# Main.net
KiCad netlist of a schematic drawn in Altium Designer
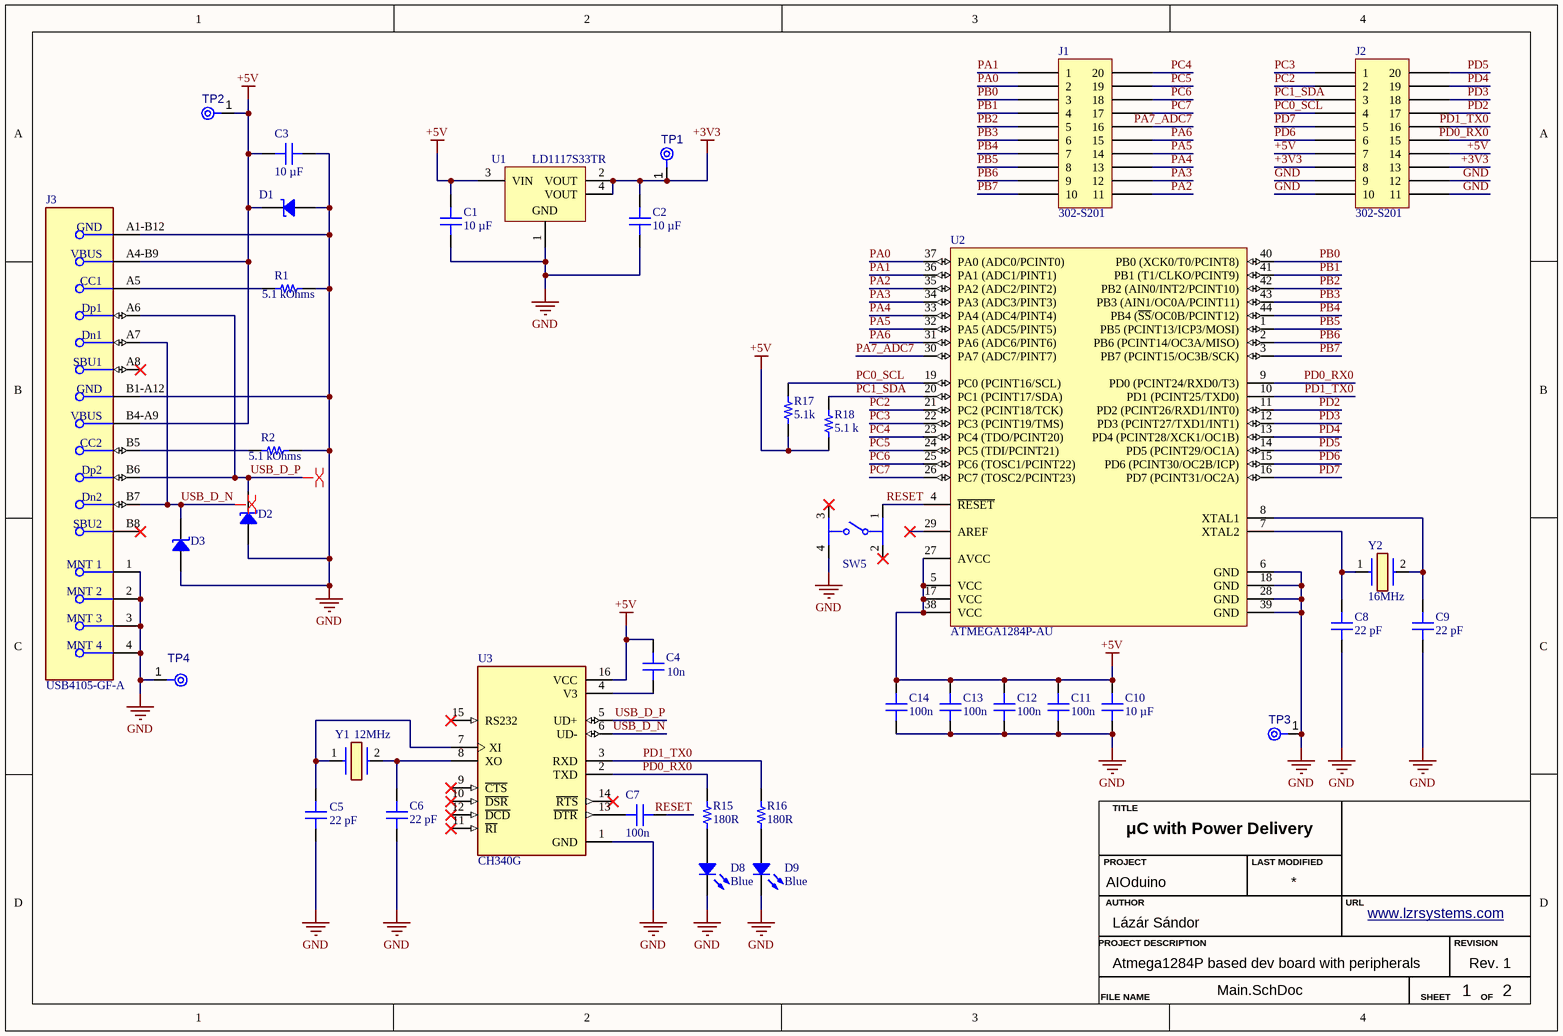
[diagram p0: Main.SchDoc]

(export (version "E")
  (design (tool "Eeschema 10.0.6"))
  (components
    (comp (ref "C1")
      (value "10 µF")
      (footprint "CAP 1206_3216 - 0.8MM")
      (description "CAP CER 10UF 35V X5R 1206")
      (fields
        (field (name "PART NUMBER") "GRT31CR6YA106KE01K")
        (field (name "CAPACITANCE") "10 µF")
        (field (name "MANUFACTURER") "Murata Electronics")
      )
      (libsource (lib "Celestial Altium Library - altium_library") (part "Capacitor"))
    )
    (comp (ref "C2")
      (value "10 µF")
      (footprint "CAP 1206_3216 - 0.8MM")
      (description "CAP CER 10UF 35V X5R 1206")
      (fields
        (field (name "PART NUMBER") "GRT31CR6YA106KE01K")
        (field (name "CAPACITANCE") "10 µF")
        (field (name "MANUFACTURER") "Murata Electronics")
      )
      (libsource (lib "Celestial Altium Library - altium_library") (part "Capacitor"))
    )
    (comp (ref "C3")
      (value "10 µF")
      (footprint "CAP 1206_3216 - 0.8MM")
      (description "CAP CER 10UF 35V X5R 1206")
      (fields
        (field (name "PART NUMBER") "GRT31CR6YA106KE01K")
        (field (name "CAPACITANCE") "10 µF")
        (field (name "MANUFACTURER") "Murata Electronics")
      )
      (libsource (lib "Celestial Altium Library - altium_library") (part "Capacitor"))
    )
    (comp (ref "C4")
      (value "10000 pF")
      (footprint "CAP 0805_2012")
      (description "CAP CER 0805 10NF 100V X7R")
      (fields
        (field (name "PART NUMBER") "C0805X103K1RAC3316")
        (field (name "CAPACITANCE") "10n")
        (field (name "MANUFACTURER") "KEMET")
      )
      (libsource (lib "Celestial Altium Library - altium_library") (part "Capacitor"))
    )
    (comp (ref "C5")
      (value "22 pF")
      (footprint "CAP 0805_2012")
      (description "CAP CER 22PF 50V C0G/NP0 0805")
      (fields
        (field (name "PART NUMBER") "C0805C220J5GACAUTO")
        (field (name "CAPACITANCE") "22 pF")
        (field (name "MANUFACTURER") "KEMET")
      )
      (libsource (lib "Celestial Altium Library - altium_library") (part "Capacitor"))
    )
    (comp (ref "C6")
      (value "22 pF")
      (footprint "CAP 0805_2012")
      (description "CAP CER 22PF 50V C0G/NP0 0805")
      (fields
        (field (name "PART NUMBER") "C0805C220J5GACAUTO")
        (field (name "CAPACITANCE") "22 pF")
        (field (name "MANUFACTURER") "KEMET")
      )
      (libsource (lib "Celestial Altium Library - altium_library") (part "Capacitor"))
    )
    (comp (ref "C7")
      (value "0.1 µF")
      (footprint "CAP 0805_2012")
      (description "CAP CER 0.1UF 50V X7R 0805")
      (fields
        (field (name "PART NUMBER") "CC0805MRX7R9BB104")
        (field (name "CAPACITANCE") "100n")
        (field (name "MANUFACTURER") "Yageo")
      )
      (libsource (lib "Celestial Altium Library - altium_library") (part "Capacitor"))
    )
    (comp (ref "C8")
      (value "22 pF")
      (footprint "CAP 0805_2012")
      (description "CAP CER 22PF 50V C0G/NP0 0805")
      (fields
        (field (name "PART NUMBER") "C0805C220J5GACAUTO")
        (field (name "CAPACITANCE") "22 pF")
        (field (name "MANUFACTURER") "KEMET")
      )
      (libsource (lib "Celestial Altium Library - altium_library") (part "Capacitor"))
    )
    (comp (ref "C9")
      (value "22 pF")
      (footprint "CAP 0805_2012")
      (description "CAP CER 22PF 50V C0G/NP0 0805")
      (fields
        (field (name "PART NUMBER") "C0805C220J5GACAUTO")
        (field (name "CAPACITANCE") "22 pF")
        (field (name "MANUFACTURER") "KEMET")
      )
      (libsource (lib "Celestial Altium Library - altium_library") (part "Capacitor"))
    )
    (comp (ref "C10")
      (value "10 µF")
      (footprint "CAP 1206_3216 - 0.8MM")
      (description "CAP CER 10UF 35V X5R 1206")
      (fields
        (field (name "PART NUMBER") "GRT31CR6YA106KE01K")
        (field (name "CAPACITANCE") "10 µF")
        (field (name "MANUFACTURER") "Murata Electronics")
      )
      (libsource (lib "Celestial Altium Library - altium_library") (part "Capacitor"))
    )
    (comp (ref "C11")
      (value "0.1 µF")
      (footprint "CAP 0805_2012")
      (description "CAP CER 0.1UF 50V X7R 0805")
      (fields
        (field (name "PART NUMBER") "CC0805MRX7R9BB104")
        (field (name "CAPACITANCE") "100n")
        (field (name "MANUFACTURER") "Yageo")
      )
      (libsource (lib "Celestial Altium Library - altium_library") (part "Capacitor"))
    )
    (comp (ref "C12")
      (value "0.1 µF")
      (footprint "CAP 0805_2012")
      (description "CAP CER 0.1UF 50V X7R 0805")
      (fields
        (field (name "PART NUMBER") "CC0805MRX7R9BB104")
        (field (name "CAPACITANCE") "100n")
        (field (name "MANUFACTURER") "Yageo")
      )
      (libsource (lib "Celestial Altium Library - altium_library") (part "Capacitor"))
    )
    (comp (ref "C13")
      (value "0.1 µF")
      (footprint "CAP 0805_2012")
      (description "CAP CER 0.1UF 50V X7R 0805")
      (fields
        (field (name "PART NUMBER") "CC0805MRX7R9BB104")
        (field (name "CAPACITANCE") "100n")
        (field (name "MANUFACTURER") "Yageo")
      )
      (libsource (lib "Celestial Altium Library - altium_library") (part "Capacitor"))
    )
    (comp (ref "C14")
      (value "0.1 µF")
      (footprint "CAP 0805_2012")
      (description "CAP CER 0.1UF 50V X7R 0805")
      (fields
        (field (name "PART NUMBER") "CC0805MRX7R9BB104")
        (field (name "CAPACITANCE") "100n")
        (field (name "MANUFACTURER") "Yageo")
      )
      (libsource (lib "Celestial Altium Library - altium_library") (part "Capacitor"))
    )
    (comp (ref "D1")
      (value "PESD5V0S1UB,115")
      (footprint "SOD523F")
      (description "TVS DIODE 5VWM 20VC SOD523")
      (fields (field (name "MANUFACTURER") "Nexperia USA Inc."))
      (libsource (lib "Celestial Altium Library - altium_library") (part "DIODE TVS UNI"))
    )
    (comp (ref "D2")
      (value "PESD5V0S1UB,115")
      (footprint "SOD523F")
      (description "TVS DIODE 5VWM 20VC SOD523")
      (fields (field (name "MANUFACTURER") "Nexperia USA Inc."))
      (libsource (lib "Celestial Altium Library - altium_library") (part "DIODE TVS UNI"))
    )
    (comp (ref "D3")
      (value "PESD5V0S1UB,115")
      (footprint "SOD523F")
      (description "TVS DIODE 5VWM 20VC SOD523")
      (fields (field (name "MANUFACTURER") "Nexperia USA Inc."))
      (libsource (lib "Celestial Altium Library - altium_library") (part "DIODE TVS UNI"))
    )
    (comp (ref "D8")
      (value "Blue")
      (footprint "LED 1206_3216 BLUE")
      (description "LED BLUE CLEAR 1206 SMD")
      (fields
        (field (name "PART NUMBER") "SML-LX1206USBC-TR")
        (field (name "MANUFACTURER") "Lumex Opto/Components Inc.")
      )
      (libsource (lib "Celestial Altium Library - altium_library") (part "LED"))
    )
    (comp (ref "D9")
      (value "Blue")
      (footprint "LED 1206_3216 BLUE")
      (description "LED BLUE CLEAR 1206 SMD")
      (fields
        (field (name "PART NUMBER") "SML-LX1206USBC-TR")
        (field (name "MANUFACTURER") "Lumex Opto/Components Inc.")
      )
      (libsource (lib "Celestial Altium Library - altium_library") (part "LED"))
    )
    (comp (ref "J1")
      (value "302-S201")
      (footprint "OST 302-S201")
      (description "CONN HEADER VERT 20POS 2.54MM")
      (fields (field (name "MANUFACTURER") "On Shore Technology Inc."))
      (libsource (lib "Celestial Altium Library - altium_library") (part "20 Pin Dual Row"))
    )
    (comp (ref "J2")
      (value "302-S201")
      (footprint "OST 302-S201")
      (description "CONN HEADER VERT 20POS 2.54MM")
      (fields (field (name "MANUFACTURER") "On Shore Technology Inc."))
      (libsource (lib "Celestial Altium Library - altium_library") (part "20 Pin Dual Row"))
    )
    (comp (ref "J3")
      (value "USB4105-GF-A")
      (footprint "FP-USB4105-GF-A-MFG")
      (description "Conn USB 2.0 Type C RCP 24 POS 0.3mm/0.5mm Solder RA SMD 24 Terminal 1 Port T/R")
      (libsource (lib "Sandor Lazar") (part "e7c17a616881a82b79941196b4bec10"))
    )
    (comp (ref "R1")
      (value "5.1 kOhms")
      (footprint "RES 0805_2012")
      (description "RES 5.1K OHM 1% 1/8W 0805")
      (fields
        (field (name "PART NUMBER") "RMCF0805FT5K10")
        (field (name "MANUFACTURER") "Stackpole Electronics Inc")
      )
      (libsource (lib "Celestial Altium Library - altium_library") (part "Resistor"))
    )
    (comp (ref "R2")
      (value "5.1 kOhms")
      (footprint "RES 0805_2012")
      (description "RES 5.1K OHM 1% 1/8W 0805")
      (fields
        (field (name "PART NUMBER") "RMCF0805FT5K10")
        (field (name "MANUFACTURER") "Stackpole Electronics Inc")
      )
      (libsource (lib "Celestial Altium Library - altium_library") (part "Resistor"))
    )
    (comp (ref "R15")
      (value "180R")
      (footprint "RES 0805_2012")
      (description "RES SMD 180 OHM 1% 1/2W 0805")
      (fields (field (name "PART NUMBER") "CRCW0805180RFKEAHP") (field (name "MANUFACTURER") "Vishay Dale"))
      (libsource (lib "Celestial Altium Library - altium_library") (part "Resistor"))
    )
    (comp (ref "R16")
      (value "180R")
      (footprint "RES 0805_2012")
      (description "RES SMD 180 OHM 1% 1/2W 0805")
      (fields (field (name "PART NUMBER") "CRCW0805180RFKEAHP") (field (name "MANUFACTURER") "Vishay Dale"))
      (libsource (lib "Celestial Altium Library - altium_library") (part "Resistor"))
    )
    (comp (ref "R17")
      (value "5.1k")
      (footprint "RES 0805_2012")
      (description "RES 5.1K OHM 1% 1/8W 0805")
      (fields
        (field (name "PART NUMBER") "RMCF0805FT5K10")
        (field (name "MANUFACTURER") "Stackpole Electronics Inc")
      )
      (libsource (lib "Celestial Altium Library - altium_library") (part "Resistor"))
    )
    (comp (ref "R18")
      (value "5.1 k")
      (footprint "RES 0805_2012")
      (description "RES 5.1K OHM 1% 1/8W 0805")
      (fields
        (field (name "PART NUMBER") "RMCF0805FT5K10")
        (field (name "MANUFACTURER") "Stackpole Electronics Inc")
      )
      (libsource (lib "Celestial Altium Library - altium_library") (part "Resistor"))
    )
    (comp (ref "SW5")
      (value "PTS526SK15SMTR2LFS")
      (footprint "FP-PTS526SK15SMTR2LFS-MFG")
      (description "Switch Tactile N.O. SPST Round Button Gull Wing 0.05A 12VDC 200000Cycles 2.45N SMD T/R")
      (libsource (lib "Sandor Lazar") (part "b8895f3f4cefb76e1819d2863dba89b"))
    )
    (comp (ref "TP1")
      (value "TPAD6R")
      (footprint "TP06R")
      (description "0.6mm round")
      (libsource (lib "Sandor Lazar") (part "CMP-001-0001-4"))
    )
    (comp (ref "TP2")
      (value "TPAD6R")
      (footprint "TP06R")
      (description "0.6mm round")
      (libsource (lib "Sandor Lazar") (part "CMP-001-0001-4"))
    )
    (comp (ref "TP3")
      (value "TPAD6R")
      (footprint "TP06R")
      (description "0.6mm round")
      (libsource (lib "Sandor Lazar") (part "CMP-001-0001-4"))
    )
    (comp (ref "TP4")
      (value "TPAD6R")
      (footprint "TP06R")
      (description "0.6mm round")
      (libsource (lib "Sandor Lazar") (part "CMP-001-0001-4"))
    )
    (comp (ref "U1")
      (value "LD1117S33TR")
      (footprint "STM-SOT-223_M")
      (fields (field (name "POWER") "12W") (field (name "MANUFACTURER") "STMicroelectronics"))
      (libsource (lib "Sandor Lazar") (part "STM-LD1117-SOT223-4"))
    )
    (comp (ref "U2")
      (value "ATMEGA1284P-AU")
      (footprint "ATML-44A_M")
      (fields (field (name "MANUFACTURER") "Atmel"))
      (libsource (lib "Sandor Lazar") (part "ATML-ATMEGA1284P-AU-TQFP-44"))
    )
    (comp (ref "U3")
      (value "CH340G")
      (footprint "SOIC127P600X180-16N")
      (description "USB Interface Integrated Circuit")
      (fields (field (name "MF") "WCH") (field (name "MP") "Ch340G"))
      (libsource (lib "Sandor Lazar") (part "CH340G"))
    )
    (comp (ref "Y1")
      (value "12MHz")
      (footprint "SamacSys:ECS160184XCKM")
      (description "Crystal or Oscillator")
      (fields
        (field (name "MANUFACTURER_PART_NUMBER") "ECS-160-18-4X-CKM")
        (field (name "MOUSER PART NUMBER") "520-ECS160-18-4X-CKM")
      )
      (libsource (lib "*") (part "ECS-160-18-4X-CKM"))
    )
    (comp (ref "Y2")
      (value "16MHz")
      (footprint "SamacSys:ECS160184XCKM")
      (description "Crystal or Oscillator")
      (fields
        (field (name "MANUFACTURER_PART_NUMBER") "ECS-160-18-4X-CKM")
        (field (name "MOUSER PART NUMBER") "520-ECS160-18-4X-CKM")
      )
      (libsource (lib "*") (part "ECS-160-18-4X-CKM"))
    )
  )
  (nets
    (net (code "1") (name "+3V3") (class "Default")
      (node (ref "C2") (pin "2") (pinfunction "2_2") (pintype "passive"))
      (node (ref "J2") (pin "13") (pinfunction "13_13") (pintype "passive"))
      (node (ref "J2") (pin "8") (pinfunction "8_8") (pintype "passive"))
      (node (ref "TP1") (pin "1") (pinfunction "TP_1") (pintype "passive"))
      (node (ref "U1") (pin "2") (pinfunction "VOUT_2") (pintype "power_in"))
      (node (ref "U1") (pin "4") (pinfunction "VOUT_4") (pintype "power_in"))
    )
    (net (code "2") (name "+5V") (class "Default")
      (node (ref "C1") (pin "2") (pinfunction "2_2") (pintype "passive"))
      (node (ref "C10") (pin "2") (pinfunction "2_2") (pintype "passive"))
      (node (ref "C11") (pin "2") (pinfunction "2_2") (pintype "passive"))
      (node (ref "C12") (pin "2") (pinfunction "2_2") (pintype "passive"))
      (node (ref "C13") (pin "1") (pinfunction "1_1") (pintype "passive"))
      (node (ref "C14") (pin "2") (pinfunction "2_2") (pintype "passive"))
      (node (ref "C3") (pin "1") (pinfunction "1_1") (pintype "passive"))
      (node (ref "C4") (pin "2") (pinfunction "2_2") (pintype "passive"))
      (node (ref "D1") (pin "2") (pinfunction "2_2") (pintype "passive"))
      (node (ref "J2") (pin "14") (pinfunction "14_14") (pintype "passive"))
      (node (ref "J2") (pin "7") (pinfunction "7_7") (pintype "passive"))
      (node (ref "J3") (pin "A4-B9") (pinfunction "VBUS_A4-B9") (pintype "passive"))
      (node (ref "J3") (pin "B4-A9") (pinfunction "VBUS_B4-A9") (pintype "passive"))
      (node (ref "R17") (pin "1") (pinfunction "1_1") (pintype "passive"))
      (node (ref "R18") (pin "1") (pinfunction "1_1") (pintype "passive"))
      (node (ref "TP2") (pin "1") (pinfunction "TP_1") (pintype "passive"))
      (node (ref "U1") (pin "3") (pinfunction "VIN_3") (pintype "power_in"))
      (node (ref "U2") (pin "17") (pinfunction "VCC_17") (pintype "power_in"))
      (node (ref "U2") (pin "27") (pinfunction "AVCC_27") (pintype "power_in"))
      (node (ref "U2") (pin "38") (pinfunction "VCC_38") (pintype "power_in"))
      (node (ref "U2") (pin "5") (pinfunction "VCC_5") (pintype "power_in"))
      (node (ref "U3") (pin "16") (pinfunction "VCC_16") (pintype "power_in"))
    )
    (net (code "3") (name "/PA0") (class "Default")
      (node (ref "J1") (pin "2") (pinfunction "2_2") (pintype "passive"))
      (node (ref "U2") (pin "37") (pinfunction "PA0_(ADC0/PCINT0)_37") (pintype "bidirectional"))
    )
    (net (code "4") (name "/PA1") (class "Default")
      (node (ref "J1") (pin "1") (pinfunction "1_1") (pintype "passive"))
      (node (ref "U2") (pin "36") (pinfunction "PA1_(ADC1/PINT1)_36") (pintype "bidirectional"))
    )
    (net (code "5") (name "/PA2") (class "Default")
      (node (ref "J1") (pin "11") (pinfunction "11_11") (pintype "passive"))
      (node (ref "U2") (pin "35") (pinfunction "PA2_(ADC2/PINT2)_35") (pintype "bidirectional"))
    )
    (net (code "6") (name "/PA3") (class "Default")
      (node (ref "J1") (pin "12") (pinfunction "12_12") (pintype "passive"))
      (node (ref "U2") (pin "34") (pinfunction "PA3_(ADC3/PINT3)_34") (pintype "bidirectional"))
    )
    (net (code "7") (name "/PA4") (class "Default")
      (node (ref "J1") (pin "13") (pinfunction "13_13") (pintype "passive"))
      (node (ref "U2") (pin "33") (pinfunction "PA4_(ADC4/PINT4)_33") (pintype "bidirectional"))
    )
    (net (code "8") (name "/PA5") (class "Default")
      (node (ref "J1") (pin "14") (pinfunction "14_14") (pintype "passive"))
      (node (ref "U2") (pin "32") (pinfunction "PA5_(ADC5/PINT5)_32") (pintype "bidirectional"))
    )
    (net (code "9") (name "/PA6") (class "Default")
      (node (ref "J1") (pin "15") (pinfunction "15_15") (pintype "passive"))
      (node (ref "U2") (pin "31") (pinfunction "PA6_(ADC6/PINT6)_31") (pintype "bidirectional"))
    )
    (net (code "10") (name "/PA7_ADC7") (class "Default")
      (node (ref "J1") (pin "16") (pinfunction "16_16") (pintype "passive"))
      (node (ref "U2") (pin "30") (pinfunction "PA7_(ADC7/PINT7)_30") (pintype "bidirectional"))
    )
    (net (code "11") (name "/PB0") (class "Default")
      (node (ref "J1") (pin "3") (pinfunction "3_3") (pintype "passive"))
      (node (ref "U2") (pin "40") (pinfunction "PB0_(XCK0/T0/PCINT8)_40") (pintype "bidirectional"))
    )
    (net (code "12") (name "/PB1") (class "Default")
      (node (ref "J1") (pin "4") (pinfunction "4_4") (pintype "passive"))
      (node (ref "U2") (pin "41") (pinfunction "PB1_(T1/CLKO/PCINT9)_41") (pintype "bidirectional"))
    )
    (net (code "13") (name "/PB2") (class "Default")
      (node (ref "J1") (pin "5") (pinfunction "5_5") (pintype "passive"))
      (node (ref "U2") (pin "42") (pinfunction "PB2_(AIN0/INT2/PCINT10)_42") (pintype "bidirectional"))
    )
    (net (code "14") (name "/PB3") (class "Default")
      (node (ref "J1") (pin "6") (pinfunction "6_6") (pintype "passive"))
      (node (ref "U2") (pin "43") (pinfunction "PB3_(AIN1/OC0A/PCINT11)_43") (pintype "bidirectional"))
    )
    (net (code "15") (name "/PB4") (class "Default")
      (node (ref "J1") (pin "7") (pinfunction "7_7") (pintype "passive"))
      (node (ref "U2") (pin "44") (pinfunction "PB4_(~{SS}/OC0B/PCINT12)_44") (pintype "bidirectional"))
    )
    (net (code "16") (name "/PB5") (class "Default")
      (node (ref "J1") (pin "8") (pinfunction "8_8") (pintype "passive"))
      (node (ref "U2") (pin "1") (pinfunction "PB5_(PCINT13/ICP3/MOSI)_1") (pintype "bidirectional"))
    )
    (net (code "17") (name "/PB6") (class "Default")
      (node (ref "J1") (pin "9") (pinfunction "9_9") (pintype "passive"))
      (node (ref "U2") (pin "2") (pinfunction "PB6_(PCINT14/OC3A/MISO)_2") (pintype "bidirectional"))
    )
    (net (code "18") (name "/PB7") (class "Default")
      (node (ref "J1") (pin "10") (pinfunction "10_10") (pintype "passive"))
      (node (ref "U2") (pin "3") (pinfunction "PB7_(PCINT15/OC3B/SCK)_3") (pintype "bidirectional"))
    )
    (net (code "19") (name "/PC0_SCL") (class "Default")
      (node (ref "J2") (pin "4") (pinfunction "4_4") (pintype "passive"))
      (node (ref "R17") (pin "2") (pinfunction "2_2") (pintype "passive"))
      (node (ref "U2") (pin "19") (pinfunction "PC0_(PCINT16/SCL)_19") (pintype "bidirectional"))
    )
    (net (code "20") (name "/PC1_SDA") (class "Default")
      (node (ref "J2") (pin "3") (pinfunction "3_3") (pintype "passive"))
      (node (ref "R18") (pin "2") (pinfunction "2_2") (pintype "passive"))
      (node (ref "U2") (pin "20") (pinfunction "PC1_(PCINT17/SDA)_20") (pintype "bidirectional"))
    )
    (net (code "21") (name "/PC2") (class "Default")
      (node (ref "J2") (pin "2") (pinfunction "2_2") (pintype "passive"))
      (node (ref "U2") (pin "21") (pinfunction "PC2_(PCINT18/TCK)_21") (pintype "bidirectional"))
    )
    (net (code "22") (name "/PC3") (class "Default")
      (node (ref "J2") (pin "1") (pinfunction "1_1") (pintype "passive"))
      (node (ref "U2") (pin "22") (pinfunction "PC3_(PCINT19/TMS)_22") (pintype "bidirectional"))
    )
    (net (code "23") (name "/PC4") (class "Default")
      (node (ref "J1") (pin "20") (pinfunction "20_20") (pintype "passive"))
      (node (ref "U2") (pin "23") (pinfunction "PC4_(TDO/PCINT20)_23") (pintype "bidirectional"))
    )
    (net (code "24") (name "/PC5") (class "Default")
      (node (ref "J1") (pin "19") (pinfunction "19_19") (pintype "passive"))
      (node (ref "U2") (pin "24") (pinfunction "PC5_(TDI/PCINT21)_24") (pintype "bidirectional"))
    )
    (net (code "25") (name "/PC6") (class "Default")
      (node (ref "J1") (pin "18") (pinfunction "18_18") (pintype "passive"))
      (node (ref "U2") (pin "25") (pinfunction "PC6_(TOSC1/PCINT22)_25") (pintype "bidirectional"))
    )
    (net (code "26") (name "/PC7") (class "Default")
      (node (ref "J1") (pin "17") (pinfunction "17_17") (pintype "passive"))
      (node (ref "U2") (pin "26") (pinfunction "PC7_(TOSC2/PCINT23)_26") (pintype "bidirectional"))
    )
    (net (code "27") (name "/PD0_RX0") (class "Default")
      (node (ref "J2") (pin "15") (pinfunction "15_15") (pintype "passive"))
      (node (ref "R15") (pin "2") (pinfunction "2_2") (pintype "passive"))
      (node (ref "U2") (pin "9") (pinfunction "PD0_(PCINT24/RXD0/T3)_9") (pintype "passive"))
      (node (ref "U3") (pin "2") (pinfunction "TXD_2") (pintype "passive"))
    )
    (net (code "28") (name "/PD1_TX0") (class "Default")
      (node (ref "J2") (pin "16") (pinfunction "16_16") (pintype "passive"))
      (node (ref "R16") (pin "2") (pinfunction "2_2") (pintype "passive"))
      (node (ref "U2") (pin "10") (pinfunction "PD1_(PCINT25/TXD0)_10") (pintype "passive"))
      (node (ref "U3") (pin "3") (pinfunction "RXD_3") (pintype "passive"))
    )
    (net (code "29") (name "/PD2") (class "Default")
      (node (ref "J2") (pin "17") (pinfunction "17_17") (pintype "passive"))
      (node (ref "U2") (pin "11") (pinfunction "PD2_(PCINT26/RXD1/INT0)_11") (pintype "bidirectional"))
    )
    (net (code "30") (name "/PD3") (class "Default")
      (node (ref "J2") (pin "18") (pinfunction "18_18") (pintype "passive"))
      (node (ref "U2") (pin "12") (pinfunction "PD3_(PCINT27/TXD1/INT1)_12") (pintype "bidirectional"))
    )
    (net (code "31") (name "/PD4") (class "Default")
      (node (ref "J2") (pin "19") (pinfunction "19_19") (pintype "passive"))
      (node (ref "U2") (pin "13") (pinfunction "PD4_(PCINT28/XCK1/OC1B)_13") (pintype "bidirectional"))
    )
    (net (code "32") (name "/PD5") (class "Default")
      (node (ref "J2") (pin "20") (pinfunction "20_20") (pintype "passive"))
      (node (ref "U2") (pin "14") (pinfunction "PD5_(PCINT29/OC1A)_14") (pintype "bidirectional"))
    )
    (net (code "33") (name "/PD6") (class "Default")
      (node (ref "J2") (pin "6") (pinfunction "6_6") (pintype "passive"))
      (node (ref "U2") (pin "15") (pinfunction "PD6_(PCINT30/OC2B/ICP)_15") (pintype "bidirectional"))
    )
    (net (code "34") (name "/PD7") (class "Default")
      (node (ref "J2") (pin "5") (pinfunction "5_5") (pintype "passive"))
      (node (ref "U2") (pin "16") (pinfunction "PD7_(PCINT31/OC2A)_16") (pintype "bidirectional"))
    )
    (net (code "35") (name "/RESET") (class "Default")
      (node (ref "C7") (pin "2") (pinfunction "2_2") (pintype "passive"))
      (node (ref "SW5") (pin "1") (pinfunction "1_1") (pintype "passive"))
      (node (ref "U2") (pin "4") (pinfunction "~{RESET}_4") (pintype "passive"))
    )
    (net (code "36") (name "/USB_D_N") (class "Default")
      (node (ref "D3") (pin "2") (pinfunction "2_2") (pintype "passive"))
      (node (ref "J3") (pin "A7") (pinfunction "Dn1_A7") (pintype "bidirectional"))
      (node (ref "J3") (pin "B7") (pinfunction "Dn2_B7") (pintype "bidirectional"))
      (node (ref "U3") (pin "6") (pinfunction "UD-_6") (pintype "bidirectional"))
    )
    (net (code "37") (name "/USB_D_P") (class "Default")
      (node (ref "D2") (pin "2") (pinfunction "2_2") (pintype "passive"))
      (node (ref "J3") (pin "A6") (pinfunction "Dp1_A6") (pintype "bidirectional"))
      (node (ref "J3") (pin "B6") (pinfunction "Dp2_B6") (pintype "bidirectional"))
      (node (ref "U3") (pin "5") (pinfunction "UD+_5") (pintype "bidirectional"))
    )
    (net (code "38") (name "GND") (class "Default")
      (node (ref "C1") (pin "1") (pinfunction "1_1") (pintype "passive"))
      (node (ref "C10") (pin "1") (pinfunction "1_1") (pintype "passive"))
      (node (ref "C11") (pin "1") (pinfunction "1_1") (pintype "passive"))
      (node (ref "C12") (pin "1") (pinfunction "1_1") (pintype "passive"))
      (node (ref "C13") (pin "2") (pinfunction "2_2") (pintype "passive"))
      (node (ref "C14") (pin "1") (pinfunction "1_1") (pintype "passive"))
      (node (ref "C2") (pin "1") (pinfunction "1_1") (pintype "passive"))
      (node (ref "C3") (pin "2") (pinfunction "2_2") (pintype "passive"))
      (node (ref "C5") (pin "1") (pinfunction "1_1") (pintype "passive"))
      (node (ref "C6") (pin "1") (pinfunction "1_1") (pintype "passive"))
      (node (ref "C8") (pin "1") (pinfunction "1_1") (pintype "passive"))
      (node (ref "C9") (pin "1") (pinfunction "1_1") (pintype "passive"))
      (node (ref "D1") (pin "1") (pinfunction "1_1") (pintype "passive"))
      (node (ref "D2") (pin "1") (pinfunction "1_1") (pintype "passive"))
      (node (ref "D3") (pin "1") (pinfunction "1_1") (pintype "passive"))
      (node (ref "D8") (pin "2") (pinfunction "2_2") (pintype "passive"))
      (node (ref "D9") (pin "2") (pinfunction "2_2") (pintype "passive"))
      (node (ref "J2") (pin "10") (pinfunction "10_10") (pintype "passive"))
      (node (ref "J2") (pin "11") (pinfunction "11_11") (pintype "passive"))
      (node (ref "J2") (pin "12") (pinfunction "12_12") (pintype "passive"))
      (node (ref "J2") (pin "9") (pinfunction "9_9") (pintype "passive"))
      (node (ref "J3") (pin "1") (pinfunction "MNT_1_1") (pintype "passive"))
      (node (ref "J3") (pin "2") (pinfunction "MNT_2_2") (pintype "passive"))
      (node (ref "J3") (pin "3") (pinfunction "MNT_3_3") (pintype "passive"))
      (node (ref "J3") (pin "4") (pinfunction "MNT_4_4") (pintype "passive"))
      (node (ref "J3") (pin "A1-B12") (pinfunction "GND_A1-B12") (pintype "passive"))
      (node (ref "J3") (pin "B1-A12") (pinfunction "GND_B1-A12") (pintype "passive"))
      (node (ref "R1") (pin "2") (pinfunction "2_2") (pintype "passive"))
      (node (ref "R2") (pin "2") (pinfunction "2_2") (pintype "passive"))
      (node (ref "SW5") (pin "4") (pinfunction "4_4") (pintype "passive"))
      (node (ref "TP3") (pin "1") (pinfunction "TP_1") (pintype "passive"))
      (node (ref "TP4") (pin "1") (pinfunction "TP_1") (pintype "passive"))
      (node (ref "U1") (pin "1") (pinfunction "GND_1") (pintype "power_in"))
      (node (ref "U2") (pin "18") (pinfunction "GND_18") (pintype "passive"))
      (node (ref "U2") (pin "28") (pinfunction "GND_28") (pintype "passive"))
      (node (ref "U2") (pin "39") (pinfunction "GND_39") (pintype "passive"))
      (node (ref "U2") (pin "6") (pinfunction "GND_6") (pintype "passive"))
      (node (ref "U3") (pin "1") (pinfunction "GND_1") (pintype "power_in"))
    )
    (net (code "39") (name "Net-(D8-Pad1)") (class "Default")
      (node (ref "D8") (pin "1") (pinfunction "1_1") (pintype "passive"))
      (node (ref "R15") (pin "1") (pinfunction "1_1") (pintype "passive"))
    )
    (net (code "40") (name "Net-(D9-Pad1)") (class "Default")
      (node (ref "D9") (pin "1") (pinfunction "1_1") (pintype "passive"))
      (node (ref "R16") (pin "1") (pinfunction "1_1") (pintype "passive"))
    )
    (net (code "41") (name "Net-(J3-CC1)") (class "Default")
      (node (ref "J3") (pin "A5") (pinfunction "CC1_A5") (pintype "passive"))
      (node (ref "R1") (pin "1") (pinfunction "1_1") (pintype "passive"))
    )
    (net (code "42") (name "Net-(J3-CC2)") (class "Default")
      (node (ref "J3") (pin "B5") (pinfunction "CC2_B5") (pintype "bidirectional"))
      (node (ref "R2") (pin "1") (pinfunction "1_1") (pintype "passive"))
    )
    (net (code "43") (name "Net-(U2-XTAL1)") (class "Default")
      (node (ref "C9") (pin "2") (pinfunction "2_2") (pintype "passive"))
      (node (ref "U2") (pin "8") (pinfunction "XTAL1_8") (pintype "passive"))
      (node (ref "Y2") (pin "2") (pinfunction "CRYSTAL_2_2") (pintype "passive"))
    )
    (net (code "44") (name "Net-(U2-XTAL2)") (class "Default")
      (node (ref "C8") (pin "2") (pinfunction "2_2") (pintype "passive"))
      (node (ref "U2") (pin "7") (pinfunction "XTAL2_7") (pintype "passive"))
      (node (ref "Y2") (pin "1") (pintype "passive"))
    )
    (net (code "45") (name "Net-(U3-V3)") (class "Default")
      (node (ref "C4") (pin "1") (pinfunction "1_1") (pintype "passive"))
      (node (ref "U3") (pin "4") (pinfunction "V3_4") (pintype "power_in"))
    )
    (net (code "46") (name "Net-(U3-XI)") (class "Default")
      (node (ref "C5") (pin "2") (pinfunction "2_2") (pintype "passive"))
      (node (ref "U3") (pin "7") (pinfunction "XI_7") (pintype "passive"))
      (node (ref "Y1") (pin "1") (pintype "passive"))
    )
    (net (code "47") (name "Net-(U3-XO)") (class "Default")
      (node (ref "C6") (pin "2") (pinfunction "2_2") (pintype "passive"))
      (node (ref "U3") (pin "8") (pinfunction "XO_8") (pintype "passive"))
      (node (ref "Y1") (pin "2") (pinfunction "CRYSTAL_2_2") (pintype "passive"))
    )
    (net (code "48") (name "Net-(U3-~{DTR})") (class "Default")
      (node (ref "C7") (pin "1") (pinfunction "1_1") (pintype "passive"))
      (node (ref "U3") (pin "13") (pinfunction "~{DTR}_13") (pintype "output"))
    )
    (net (code "49") (name "unconnected-(J3-SBU1-PadA8)") (class "Default")
      (node (ref "J3") (pin "A8") (pinfunction "SBU1_A8") (pintype "bidirectional+no_connect"))
    )
    (net (code "50") (name "unconnected-(J3-SBU2-PadB8)") (class "Default")
      (node (ref "J3") (pin "B8") (pinfunction "SBU2_B8") (pintype "power_in+no_connect"))
    )
    (net (code "51") (name "unconnected-(SW5-Pad2)") (class "Default")
      (node (ref "SW5") (pin "2") (pinfunction "2_2") (pintype "passive+no_connect"))
    )
    (net (code "52") (name "unconnected-(SW5-Pad3)") (class "Default")
      (node (ref "SW5") (pin "3") (pinfunction "3_3") (pintype "passive+no_connect"))
    )
    (net (code "53") (name "unconnected-(U2-AREF-Pad29)") (class "Default")
      (node (ref "U2") (pin "29") (pinfunction "AREF_29") (pintype "passive+no_connect"))
    )
    (net (code "54") (name "unconnected-(U3-RS232-Pad15)") (class "Default")
      (node (ref "U3") (pin "15") (pinfunction "RS232_15") (pintype "input+no_connect"))
    )
    (net (code "55") (name "unconnected-(U3-~{CTS}-Pad9)") (class "Default")
      (node (ref "U3") (pin "9") (pinfunction "~{CTS}_9") (pintype "input+no_connect"))
    )
    (net (code "56") (name "unconnected-(U3-~{DCD}-Pad12)") (class "Default")
      (node (ref "U3") (pin "12") (pinfunction "~{DCD}_12") (pintype "input+no_connect"))
    )
    (net (code "57") (name "unconnected-(U3-~{DSR}-Pad10)") (class "Default")
      (node (ref "U3") (pin "10") (pinfunction "~{DSR}_10") (pintype "input+no_connect"))
    )
    (net (code "58") (name "unconnected-(U3-~{RI}-Pad11)") (class "Default")
      (node (ref "U3") (pin "11") (pinfunction "~{RI}_11") (pintype "input+no_connect"))
    )
    (net (code "59") (name "unconnected-(U3-~{RTS}-Pad14)") (class "Default")
      (node (ref "U3") (pin "14") (pinfunction "~{RTS}_14") (pintype "output+no_connect"))
    )
  )
)
